# ES-2144_LPF_Module.net
KiCad netlist of a schematic drawn in EAGLE
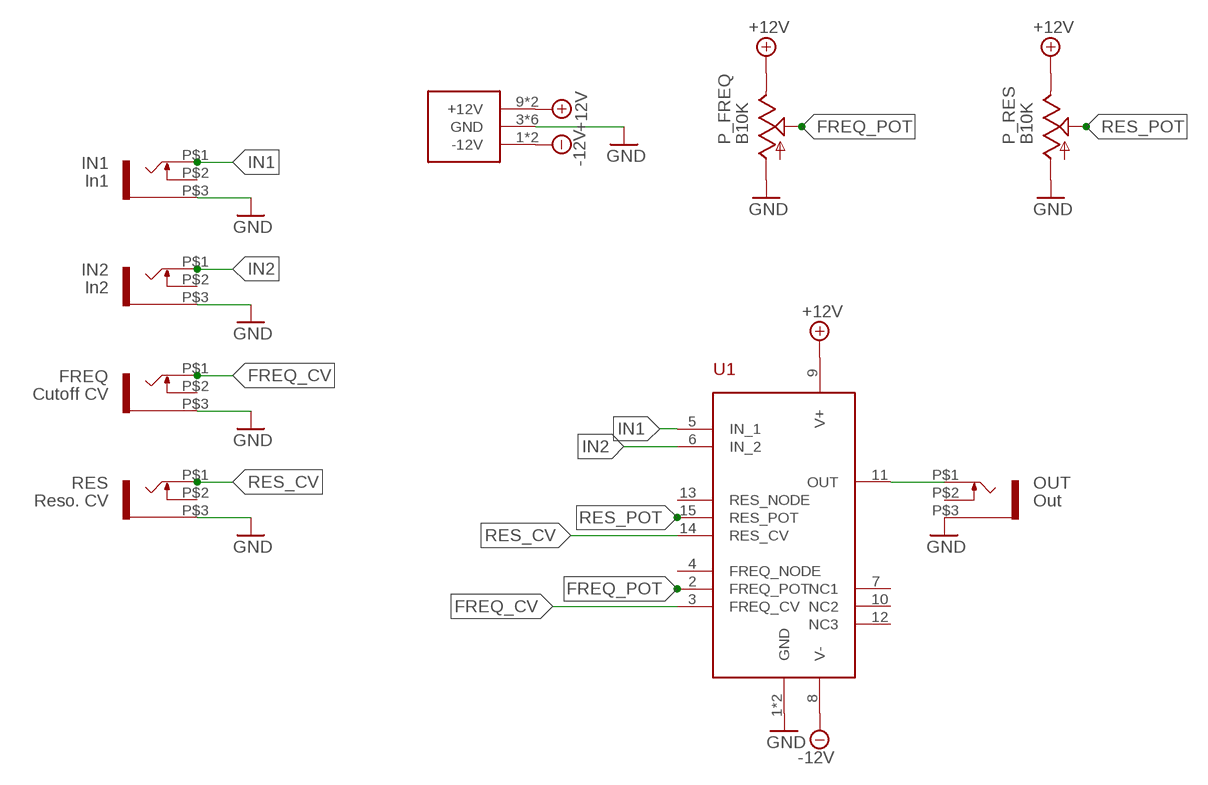
[diagram p0: schematic, sheet 1]

(export (version "E")
  (design (tool "Eeschema 10.0.6"))
  (components
    (comp (ref "FREQ")
      (value "Cutoff CV")
      (footprint "eagle-import:THONKICONN_WQP-PJ301M-12_JACK")
      (libsource (lib "eagle-import") (part "THONKICONN_WQP-PJ301M-12_JACK"))
    )
    (comp (ref "IN1")
      (value "In1")
      (footprint "eagle-import:THONKICONN_WQP-PJ301M-12_JACK")
      (libsource (lib "eagle-import") (part "THONKICONN_WQP-PJ301M-12_JACK"))
    )
    (comp (ref "IN2")
      (value "In2")
      (footprint "eagle-import:THONKICONN_WQP-PJ301M-12_JACK")
      (libsource (lib "eagle-import") (part "THONKICONN_WQP-PJ301M-12_JACK"))
    )
    (comp (ref "OUT")
      (value "Out")
      (footprint "eagle-import:THONKICONN_WQP-PJ301M-12_JACK")
      (libsource (lib "eagle-import") (part "THONKICONN_WQP-PJ301M-12_JACK"))
    )
    (comp (ref "P_FREQ")
      (value "B10K")
      (footprint "eagle-import:MUSICTHINGMODULAR_9MM_SNAP-IN_POT")
      (libsource (lib "eagle-import") (part "MUSICTHINGMODULAR_9MM_SNAP-IN_POT_"))
    )
    (comp (ref "P_RES")
      (value "B10K")
      (footprint "eagle-import:MUSICTHINGMODULAR_9MM_SNAP-IN_POT")
      (libsource (lib "eagle-import") (part "MUSICTHINGMODULAR_9MM_SNAP-IN_POT_"))
    )
    (comp (ref "RES")
      (value "Reso. CV")
      (footprint "eagle-import:THONKICONN_WQP-PJ301M-12_JACK")
      (libsource (lib "eagle-import") (part "THONKICONN_WQP-PJ301M-12_JACK"))
    )
    (comp (ref "U$1")
      (value "POWER_SIMPLE10")
      (footprint "eagle-import:POWER_10")
      (libsource (lib "eagle-import") (part "POWER_SIMPLE10"))
    )
    (comp (ref "U1")
      (value "ES_2144_V2")
      (footprint "eagle-import:ES_2144_V2")
      (libsource (lib "eagle-import") (part "ES_2144_V2"))
    )
  )
  (nets
    (net (code "1") (name "+12V") (class "Default")
      (node (ref "P_FREQ") (pin "3") (pinfunction "E_3") (pintype "passive"))
      (node (ref "P_RES") (pin "3") (pinfunction "E_3") (pintype "passive"))
      (node (ref "U$1") (pin "10") (pinfunction "+12V_10") (pintype "bidirectional"))
      (node (ref "U$1") (pin "9") (pinfunction "+12V_9") (pintype "bidirectional"))
      (node (ref "U1") (pin "9") (pinfunction "V+_9") (pintype "bidirectional"))
    )
    (net (code "2") (name "-12V") (class "Default")
      (node (ref "U$1") (pin "1") (pinfunction "-12V_1") (pintype "bidirectional"))
      (node (ref "U$1") (pin "2") (pinfunction "-12V_2") (pintype "bidirectional"))
      (node (ref "U1") (pin "8") (pinfunction "V-_8") (pintype "bidirectional"))
    )
    (net (code "3") (name "FREQ_CV") (class "Default")
      (node (ref "FREQ") (pin "P$1") (pinfunction "2_P$1") (pintype "passive"))
      (node (ref "U1") (pin "3") (pinfunction "FREQ_CV_3") (pintype "bidirectional"))
    )
    (net (code "4") (name "FREQ_POT") (class "Default")
      (node (ref "P_FREQ") (pin "2") (pinfunction "S_2") (pintype "passive"))
      (node (ref "U1") (pin "2") (pinfunction "FREQ_POT_2") (pintype "bidirectional"))
    )
    (net (code "5") (name "GND") (class "Default")
      (node (ref "FREQ") (pin "P$3") (pinfunction "1_P$3") (pintype "passive"))
      (node (ref "IN1") (pin "P$3") (pinfunction "1_P$3") (pintype "passive"))
      (node (ref "IN2") (pin "P$3") (pinfunction "1_P$3") (pintype "passive"))
      (node (ref "OUT") (pin "P$3") (pinfunction "1_P$3") (pintype "passive"))
      (node (ref "P_FREQ") (pin "1") (pinfunction "A_1") (pintype "passive"))
      (node (ref "P_RES") (pin "1") (pinfunction "A_1") (pintype "passive"))
      (node (ref "RES") (pin "P$3") (pinfunction "1_P$3") (pintype "passive"))
      (node (ref "U$1") (pin "3") (pinfunction "GND_3") (pintype "bidirectional"))
      (node (ref "U$1") (pin "4") (pinfunction "GND_4") (pintype "bidirectional"))
      (node (ref "U$1") (pin "5") (pinfunction "GND_5") (pintype "bidirectional"))
      (node (ref "U$1") (pin "6") (pinfunction "GND_6") (pintype "bidirectional"))
      (node (ref "U$1") (pin "7") (pinfunction "GND_7") (pintype "bidirectional"))
      (node (ref "U$1") (pin "8") (pinfunction "GND_8") (pintype "bidirectional"))
      (node (ref "U1") (pin "1") (pinfunction "GND_1") (pintype "bidirectional"))
      (node (ref "U1") (pin "16") (pinfunction "GND_16") (pintype "bidirectional"))
    )
    (net (code "6") (name "IN1") (class "Default")
      (node (ref "IN1") (pin "P$1") (pinfunction "2_P$1") (pintype "passive"))
      (node (ref "U1") (pin "5") (pinfunction "IN_1_5") (pintype "bidirectional"))
    )
    (net (code "7") (name "IN2") (class "Default")
      (node (ref "IN2") (pin "P$1") (pinfunction "2_P$1") (pintype "passive"))
      (node (ref "U1") (pin "6") (pinfunction "IN_2_6") (pintype "bidirectional"))
    )
    (net (code "8") (name "Net-(OUT-2)") (class "Default")
      (node (ref "OUT") (pin "P$1") (pinfunction "2_P$1") (pintype "passive"))
      (node (ref "U1") (pin "11") (pinfunction "OUT_11") (pintype "bidirectional"))
    )
    (net (code "9") (name "RES_CV") (class "Default")
      (node (ref "RES") (pin "P$1") (pinfunction "2_P$1") (pintype "passive"))
      (node (ref "U1") (pin "14") (pinfunction "RES_CV_14") (pintype "bidirectional"))
    )
    (net (code "10") (name "RES_POT") (class "Default")
      (node (ref "P_RES") (pin "2") (pinfunction "S_2") (pintype "passive"))
      (node (ref "U1") (pin "15") (pinfunction "RES_POT_15") (pintype "bidirectional"))
    )
    (net (code "11") (name "unconnected-(FREQ-3-PadP$2)") (class "Default")
      (node (ref "FREQ") (pin "P$2") (pinfunction "3_P$2") (pintype "passive"))
    )
    (net (code "12") (name "unconnected-(IN1-3-PadP$2)") (class "Default")
      (node (ref "IN1") (pin "P$2") (pinfunction "3_P$2") (pintype "passive"))
    )
    (net (code "13") (name "unconnected-(IN2-3-PadP$2)") (class "Default")
      (node (ref "IN2") (pin "P$2") (pinfunction "3_P$2") (pintype "passive"))
    )
    (net (code "14") (name "unconnected-(OUT-3-PadP$2)") (class "Default")
      (node (ref "OUT") (pin "P$2") (pinfunction "3_P$2") (pintype "passive"))
    )
    (net (code "15") (name "unconnected-(RES-3-PadP$2)") (class "Default")
      (node (ref "RES") (pin "P$2") (pinfunction "3_P$2") (pintype "passive"))
    )
    (net (code "16") (name "unconnected-(U1-FREQ_NODE-Pad4)") (class "Default")
      (node (ref "U1") (pin "4") (pinfunction "FREQ_NODE_4") (pintype "bidirectional"))
    )
    (net (code "17") (name "unconnected-(U1-NC1-Pad7)") (class "Default")
      (node (ref "U1") (pin "7") (pinfunction "NC1_7") (pintype "bidirectional"))
    )
    (net (code "18") (name "unconnected-(U1-NC2-Pad10)") (class "Default")
      (node (ref "U1") (pin "10") (pinfunction "NC2_10") (pintype "bidirectional"))
    )
    (net (code "19") (name "unconnected-(U1-NC3-Pad12)") (class "Default")
      (node (ref "U1") (pin "12") (pinfunction "NC3_12") (pintype "bidirectional"))
    )
    (net (code "20") (name "unconnected-(U1-RES_NODE-Pad13)") (class "Default")
      (node (ref "U1") (pin "13") (pinfunction "RES_NODE_13") (pintype "bidirectional"))
    )
  )
)
